# EXTERN.net
KiCad netlist of a schematic drawn in Altium Designer
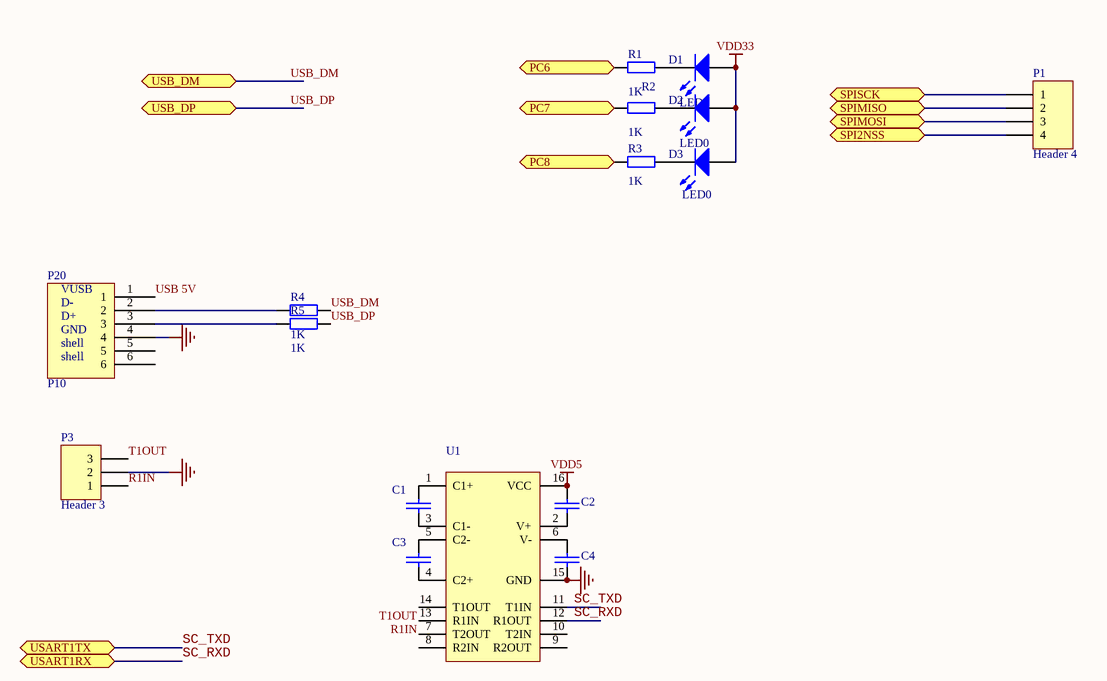
[diagram p0: EXTERN.SchDoc]

(export (version "E")
  (design (tool "Eeschema 10.0.6"))
  (components
    (comp (ref "C1")
      (value "0.1uF")
      (footprint "0805")
      (description "Capacitor")
      (libsource (lib "*") (part "CAP"))
    )
    (comp (ref "C2")
      (value "0.1uF")
      (footprint "0805")
      (description "Capacitor")
      (libsource (lib "*") (part "CAP"))
    )
    (comp (ref "C3")
      (value "0.1uF")
      (footprint "0805")
      (description "Capacitor")
      (libsource (lib "*") (part "CAP"))
    )
    (comp (ref "C4")
      (value "0.1uF")
      (footprint "0805")
      (description "Capacitor")
      (libsource (lib "*") (part "CAP"))
    )
    (comp (ref "D1")
      (value "LED0")
      (footprint "0805")
      (description "Typical INFRARED GaAs LED")
      (fields (field (name "PUBLISHER") "Altium Limited"))
      (libsource (lib "Miscellaneous Devices") (part "LED0"))
    )
    (comp (ref "D2")
      (value "LED0")
      (footprint "0805")
      (description "Typical INFRARED GaAs LED")
      (fields (field (name "PUBLISHER") "Altium Limited"))
      (libsource (lib "Miscellaneous Devices") (part "LED0"))
    )
    (comp (ref "D3")
      (value "LED0")
      (footprint "0805")
      (description "Typical INFRARED GaAs LED")
      (fields (field (name "PUBLISHER") "Altium Limited"))
      (libsource (lib "Miscellaneous Devices") (part "LED0"))
    )
    (comp (ref "P1")
      (value "Header 4")
      (footprint "HDR1X4")
      (description "Header, 4-Pin")
      (fields (field (name "PUBLISHER") "Altium Limited"))
      (libsource (lib "Miscellaneous Connectors") (part "Header 4"))
    )
    (comp (ref "P3")
      (value "Header 3")
      (footprint "HDR1X3")
      (description "Header, 3-Pin")
      (fields (field (name "PUBLISHER") "Altium Limited"))
      (libsource (lib "Miscellaneous Connectors") (part "Header 3"))
    )
    (comp (ref "P20") (value "P10") (footprint "787616") (libsource (lib "USBHeader") (part "COMPONENT_1")))
    (comp (ref "R1")
      (value "1K")
      (footprint "0805")
      (description "Resistor")
      (fields (field (name "Comment") "Res2") (field (name "PUBLISHER") "Altium Limited"))
      (libsource (lib "Miscellaneous Devices") (part "Res2"))
    )
    (comp (ref "R2")
      (value "1K")
      (footprint "0805")
      (description "Resistor")
      (fields (field (name "Comment") "Res2") (field (name "PUBLISHER") "Altium Limited"))
      (libsource (lib "Miscellaneous Devices") (part "Res2"))
    )
    (comp (ref "R3")
      (value "1K")
      (footprint "0805")
      (description "Resistor")
      (fields (field (name "Comment") "Res2") (field (name "PUBLISHER") "Altium Limited"))
      (libsource (lib "Miscellaneous Devices") (part "Res2"))
    )
    (comp (ref "R4")
      (value "1K")
      (footprint "0805")
      (description "Resistor")
      (fields (field (name "Comment") "Res2") (field (name "PUBLISHER") "Altium Limited"))
      (libsource (lib "Miscellaneous Devices") (part "Res2"))
    )
    (comp (ref "R5")
      (value "1K")
      (footprint "0805")
      (description "Resistor")
      (fields (field (name "Comment") "Res2") (field (name "PUBLISHER") "Altium Limited"))
      (libsource (lib "Miscellaneous Devices") (part "Res2"))
    )
    (comp (ref "U1") (value "MAX232-2") (footprint "SOIC16") (libsource (lib "*") (part "MAX3232-2")))
  )
  (nets
    (net (code "1") (name "/PC6") (class "Default")
      (node (ref "R1") (pin "1") (pinfunction "1_1") (pintype "passive"))
    )
    (net (code "2") (name "/PC7") (class "Default")
      (node (ref "R2") (pin "1") (pinfunction "1_1") (pintype "passive"))
    )
    (net (code "3") (name "/PC8") (class "Default")
      (node (ref "R3") (pin "1") (pinfunction "1_1") (pintype "passive"))
    )
    (net (code "4") (name "/R1IN") (class "Default")
      (node (ref "P3") (pin "1") (pinfunction "1_1") (pintype "passive"))
      (node (ref "U1") (pin "13") (pinfunction "R1IN_13") (pintype "passive"))
    )
    (net (code "5") (name "/SC_RXD") (class "Default")
      (node (ref "U1") (pin "12") (pinfunction "R1OUT_12") (pintype "passive"))
    )
    (net (code "6") (name "/SC_TXD") (class "Default")
      (node (ref "U1") (pin "11") (pinfunction "T1IN_11") (pintype "passive"))
    )
    (net (code "7") (name "/SPI2NSS") (class "Default")
      (node (ref "P1") (pin "4") (pinfunction "4_4") (pintype "passive"))
    )
    (net (code "8") (name "/SPIMISO") (class "Default")
      (node (ref "P1") (pin "2") (pinfunction "2_2") (pintype "passive"))
    )
    (net (code "9") (name "/SPIMOSI") (class "Default")
      (node (ref "P1") (pin "3") (pinfunction "3_3") (pintype "passive"))
    )
    (net (code "10") (name "/SPISCK") (class "Default")
      (node (ref "P1") (pin "1") (pinfunction "1_1") (pintype "passive"))
    )
    (net (code "11") (name "/T1OUT") (class "Default")
      (node (ref "P3") (pin "3") (pinfunction "3_3") (pintype "passive"))
      (node (ref "U1") (pin "14") (pinfunction "T1OUT_14") (pintype "passive"))
    )
    (net (code "12") (name "/USB 5V") (class "Default")
      (node (ref "P20") (pin "1") (pinfunction "1_1") (pintype "passive"))
    )
    (net (code "13") (name "/USB_DM") (class "Default")
      (node (ref "R4") (pin "2") (pinfunction "2_2") (pintype "passive"))
    )
    (net (code "14") (name "/USB_DP") (class "Default")
      (node (ref "R5") (pin "2") (pinfunction "2_2") (pintype "passive"))
    )
    (net (code "15") (name "GND") (class "Default")
      (node (ref "C4") (pin "2") (pinfunction "2_2") (pintype "passive"))
      (node (ref "P20") (pin "4") (pinfunction "4_4") (pintype "passive"))
      (node (ref "P3") (pin "2") (pinfunction "2_2") (pintype "passive"))
      (node (ref "U1") (pin "15") (pinfunction "GND_15") (pintype "passive"))
    )
    (net (code "16") (name "Net-(D1-K)") (class "Default")
      (node (ref "D1") (pin "2") (pinfunction "K_2") (pintype "passive"))
      (node (ref "R1") (pin "2") (pinfunction "2_2") (pintype "passive"))
    )
    (net (code "17") (name "Net-(D2-K)") (class "Default")
      (node (ref "D2") (pin "2") (pinfunction "K_2") (pintype "passive"))
      (node (ref "R2") (pin "2") (pinfunction "2_2") (pintype "passive"))
    )
    (net (code "18") (name "Net-(D3-K)") (class "Default")
      (node (ref "D3") (pin "2") (pinfunction "K_2") (pintype "passive"))
      (node (ref "R3") (pin "2") (pinfunction "2_2") (pintype "passive"))
    )
    (net (code "19") (name "Net-(P20-Pad2)") (class "Default")
      (node (ref "P20") (pin "2") (pinfunction "2_2") (pintype "passive"))
      (node (ref "R4") (pin "1") (pinfunction "1_1") (pintype "passive"))
    )
    (net (code "20") (name "Net-(P20-Pad3)") (class "Default")
      (node (ref "P20") (pin "3") (pinfunction "3_3") (pintype "passive"))
      (node (ref "R5") (pin "1") (pinfunction "1_1") (pintype "passive"))
    )
    (net (code "21") (name "Net-(U1-C1+)") (class "Default")
      (node (ref "C1") (pin "1") (pinfunction "1_1") (pintype "passive"))
      (node (ref "U1") (pin "1") (pinfunction "C1+_1") (pintype "passive"))
    )
    (net (code "22") (name "Net-(U1-C1-)") (class "Default")
      (node (ref "C1") (pin "2") (pinfunction "2_2") (pintype "passive"))
      (node (ref "U1") (pin "3") (pinfunction "C1-_3") (pintype "passive"))
    )
    (net (code "23") (name "Net-(U1-C2+)") (class "Default")
      (node (ref "C3") (pin "2") (pinfunction "2_2") (pintype "passive"))
      (node (ref "U1") (pin "4") (pinfunction "C2+_4") (pintype "passive"))
    )
    (net (code "24") (name "Net-(U1-C2-)") (class "Default")
      (node (ref "C3") (pin "1") (pinfunction "1_1") (pintype "passive"))
      (node (ref "U1") (pin "5") (pinfunction "C2-_5") (pintype "passive"))
    )
    (net (code "25") (name "Net-(U1-V+)") (class "Default")
      (node (ref "C2") (pin "2") (pinfunction "2_2") (pintype "passive"))
      (node (ref "U1") (pin "2") (pinfunction "V+_2") (pintype "passive"))
    )
    (net (code "26") (name "Net-(U1-V-)") (class "Default")
      (node (ref "C4") (pin "1") (pinfunction "1_1") (pintype "passive"))
      (node (ref "U1") (pin "6") (pinfunction "V-_6") (pintype "passive"))
    )
    (net (code "27") (name "VDD5") (class "Default")
      (node (ref "C2") (pin "1") (pinfunction "1_1") (pintype "passive"))
      (node (ref "U1") (pin "16") (pinfunction "VCC_16") (pintype "passive"))
    )
    (net (code "28") (name "VDD33") (class "Default")
      (node (ref "D1") (pin "1") (pinfunction "A_1") (pintype "passive"))
      (node (ref "D2") (pin "1") (pinfunction "A_1") (pintype "passive"))
      (node (ref "D3") (pin "1") (pinfunction "A_1") (pintype "passive"))
    )
    (net (code "29") (name "unconnected-(P20-Pad5)") (class "Default")
      (node (ref "P20") (pin "5") (pinfunction "5_5") (pintype "passive"))
    )
    (net (code "30") (name "unconnected-(P20-Pad6)") (class "Default")
      (node (ref "P20") (pin "6") (pinfunction "6_6") (pintype "passive"))
    )
    (net (code "31") (name "unconnected-(U1-R2IN-Pad8)") (class "Default")
      (node (ref "U1") (pin "8") (pinfunction "R2IN_8") (pintype "passive"))
    )
    (net (code "32") (name "unconnected-(U1-R2OUT-Pad9)") (class "Default")
      (node (ref "U1") (pin "9") (pinfunction "R2OUT_9") (pintype "passive"))
    )
    (net (code "33") (name "unconnected-(U1-T2IN-Pad10)") (class "Default")
      (node (ref "U1") (pin "10") (pinfunction "T2IN_10") (pintype "passive"))
    )
    (net (code "34") (name "unconnected-(U1-T2OUT-Pad7)") (class "Default")
      (node (ref "U1") (pin "7") (pinfunction "T2OUT_7") (pintype "passive"))
    )
  )
)
